# ControllerDiagrams.net
KiCad netlist of a schematic drawn in Altium Designer
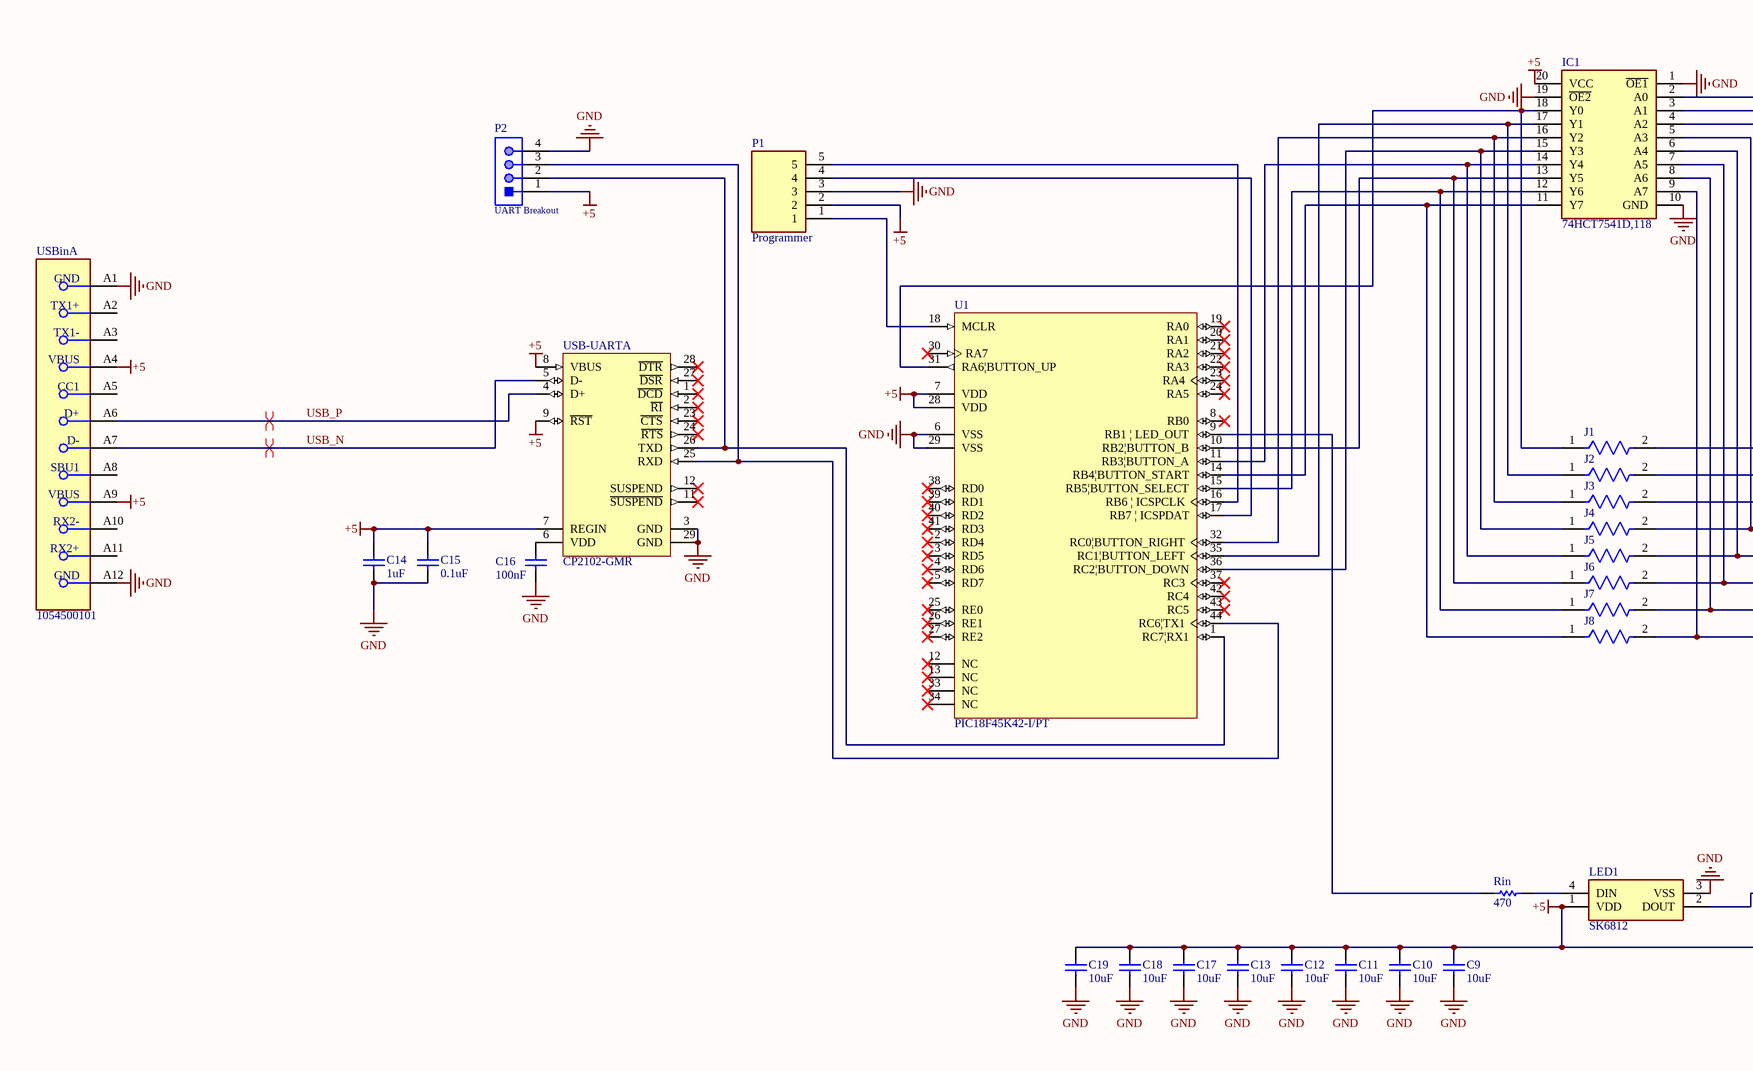
[diagram p0: ControllerDiagrams.SchDoc, left]
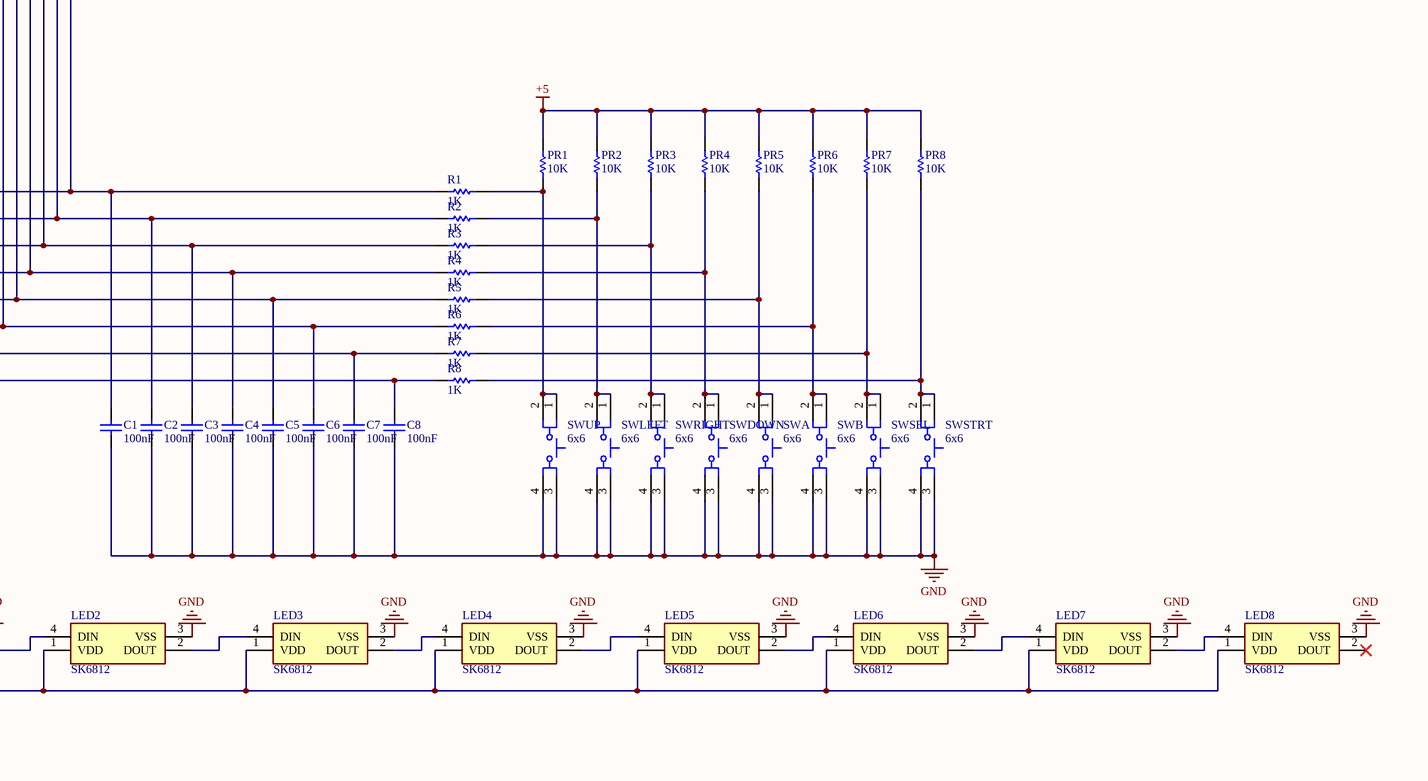
[diagram p1: ControllerDiagrams.SchDoc, right]

(export (version "E")
  (design (tool "Eeschema 10.0.6"))
  (components
    (comp (ref "C1")
      (value "100nF")
      (footprint "CAPC2013X140X50LL20T25")
      (description "Chip Capacitor, 2.2 uF, +/- 10%, 10 V, -55 to 85 degC, 0805 (2012 Metric), RoHS, Tape and Reel")
      (fields (field (name "MANUFACTURER") "AVX"))
      (libsource (lib "Altium Content Vault") (part "CAP-NP-2"))
    )
    (comp (ref "C2")
      (value "100nF")
      (footprint "CAPC2013X140X50LL20T25")
      (description "Chip Capacitor, 2.2 uF, +/- 10%, 10 V, -55 to 85 degC, 0805 (2012 Metric), RoHS, Tape and Reel")
      (fields (field (name "MANUFACTURER") "AVX"))
      (libsource (lib "Altium Content Vault") (part "CAP-NP-2"))
    )
    (comp (ref "C3")
      (value "100nF")
      (footprint "CAPC2013X140X50LL20T25")
      (description "Chip Capacitor, 2.2 uF, +/- 10%, 10 V, -55 to 85 degC, 0805 (2012 Metric), RoHS, Tape and Reel")
      (fields (field (name "MANUFACTURER") "AVX"))
      (libsource (lib "Altium Content Vault") (part "CAP-NP-2"))
    )
    (comp (ref "C4")
      (value "100nF")
      (footprint "CAPC2013X140X50LL20T25")
      (description "Chip Capacitor, 2.2 uF, +/- 10%, 10 V, -55 to 85 degC, 0805 (2012 Metric), RoHS, Tape and Reel")
      (fields (field (name "MANUFACTURER") "AVX"))
      (libsource (lib "Altium Content Vault") (part "CAP-NP-2"))
    )
    (comp (ref "C5")
      (value "100nF")
      (footprint "CAPC2013X140X50LL20T25")
      (description "Chip Capacitor, 2.2 uF, +/- 10%, 10 V, -55 to 85 degC, 0805 (2012 Metric), RoHS, Tape and Reel")
      (fields (field (name "MANUFACTURER") "AVX"))
      (libsource (lib "Altium Content Vault") (part "CAP-NP-2"))
    )
    (comp (ref "C6")
      (value "100nF")
      (footprint "CAPC2013X140X50LL20T25")
      (description "Chip Capacitor, 2.2 uF, +/- 10%, 10 V, -55 to 85 degC, 0805 (2012 Metric), RoHS, Tape and Reel")
      (fields (field (name "MANUFACTURER") "AVX"))
      (libsource (lib "Altium Content Vault") (part "CAP-NP-2"))
    )
    (comp (ref "C7")
      (value "100nF")
      (footprint "CAPC2013X140X50LL20T25")
      (description "Chip Capacitor, 2.2 uF, +/- 10%, 10 V, -55 to 85 degC, 0805 (2012 Metric), RoHS, Tape and Reel")
      (fields (field (name "MANUFACTURER") "AVX"))
      (libsource (lib "Altium Content Vault") (part "CAP-NP-2"))
    )
    (comp (ref "C8")
      (value "100nF")
      (footprint "CAPC2013X140X50LL20T25")
      (description "Chip Capacitor, 2.2 uF, +/- 10%, 10 V, -55 to 85 degC, 0805 (2012 Metric), RoHS, Tape and Reel")
      (fields (field (name "MANUFACTURER") "AVX"))
      (libsource (lib "Altium Content Vault") (part "CAP-NP-2"))
    )
    (comp (ref "C9")
      (value "10uF")
      (footprint "CAPC2013X140X50LL20T25")
      (description "Chip Capacitor, 2.2 uF, +/- 10%, 10 V, -55 to 85 degC, 0805 (2012 Metric), RoHS, Tape and Reel")
      (fields (field (name "MANUFACTURER") "AVX"))
      (libsource (lib "Altium Content Vault") (part "CAP-NP-2"))
    )
    (comp (ref "C10")
      (value "10uF")
      (footprint "CAPC2013X140X50LL20T25")
      (description "Chip Capacitor, 2.2 uF, +/- 10%, 10 V, -55 to 85 degC, 0805 (2012 Metric), RoHS, Tape and Reel")
      (fields (field (name "MANUFACTURER") "AVX"))
      (libsource (lib "Altium Content Vault") (part "CAP-NP-2"))
    )
    (comp (ref "C11")
      (value "10uF")
      (footprint "CAPC2013X140X50LL20T25")
      (description "Chip Capacitor, 2.2 uF, +/- 10%, 10 V, -55 to 85 degC, 0805 (2012 Metric), RoHS, Tape and Reel")
      (fields (field (name "MANUFACTURER") "AVX"))
      (libsource (lib "Altium Content Vault") (part "CAP-NP-2"))
    )
    (comp (ref "C12")
      (value "10uF")
      (footprint "CAPC2013X140X50LL20T25")
      (description "Chip Capacitor, 2.2 uF, +/- 10%, 10 V, -55 to 85 degC, 0805 (2012 Metric), RoHS, Tape and Reel")
      (fields (field (name "MANUFACTURER") "AVX"))
      (libsource (lib "Altium Content Vault") (part "CAP-NP-2"))
    )
    (comp (ref "C13")
      (value "10uF")
      (footprint "CAPC2013X140X50LL20T25")
      (description "Chip Capacitor, 2.2 uF, +/- 10%, 10 V, -55 to 85 degC, 0805 (2012 Metric), RoHS, Tape and Reel")
      (fields (field (name "MANUFACTURER") "AVX"))
      (libsource (lib "Altium Content Vault") (part "CAP-NP-2"))
    )
    (comp (ref "C14")
      (value "1uF")
      (footprint "CAPC2013X140X50LL20T25")
      (description "Chip Capacitor, 2.2 uF, +/- 10%, 10 V, -55 to 85 degC, 0805 (2012 Metric), RoHS, Tape and Reel")
      (fields (field (name "MANUFACTURER") "AVX"))
      (libsource (lib "Altium Content Vault") (part "CAP-NP-2"))
    )
    (comp (ref "C15")
      (value "0.1uF")
      (footprint "CAPC2013X140X50LL20T25")
      (description "Chip Capacitor, 2.2 uF, +/- 10%, 10 V, -55 to 85 degC, 0805 (2012 Metric), RoHS, Tape and Reel")
      (fields (field (name "MANUFACTURER") "AVX"))
      (libsource (lib "Altium Content Vault") (part "CAP-NP-2"))
    )
    (comp (ref "C16")
      (value "100nF")
      (footprint "CAPC2013X140X50LL20T25")
      (description "Chip Capacitor, 2.2 uF, +/- 10%, 10 V, -55 to 85 degC, 0805 (2012 Metric), RoHS, Tape and Reel")
      (fields (field (name "MANUFACTURER") "AVX"))
      (libsource (lib "Altium Content Vault") (part "CAP-NP-2"))
    )
    (comp (ref "C17")
      (value "10uF")
      (footprint "CAPC2013X140X50LL20T25")
      (description "Chip Capacitor, 2.2 uF, +/- 10%, 10 V, -55 to 85 degC, 0805 (2012 Metric), RoHS, Tape and Reel")
      (fields (field (name "MANUFACTURER") "AVX"))
      (libsource (lib "Altium Content Vault") (part "CAP-NP-2"))
    )
    (comp (ref "C18")
      (value "10uF")
      (footprint "CAPC2013X140X50LL20T25")
      (description "Chip Capacitor, 2.2 uF, +/- 10%, 10 V, -55 to 85 degC, 0805 (2012 Metric), RoHS, Tape and Reel")
      (fields (field (name "MANUFACTURER") "AVX"))
      (libsource (lib "Altium Content Vault") (part "CAP-NP-2"))
    )
    (comp (ref "C19")
      (value "10uF")
      (footprint "CAPC2013X140X50LL20T25")
      (description "Chip Capacitor, 2.2 uF, +/- 10%, 10 V, -55 to 85 degC, 0805 (2012 Metric), RoHS, Tape and Reel")
      (fields (field (name "MANUFACTURER") "AVX"))
      (libsource (lib "Altium Content Vault") (part "CAP-NP-2"))
    )
    (comp (ref "IC1")
      (value "74HCT7541D,118")
      (footprint "SamacSys:SOIC127P1032X265-20N")
      (description "Integrated Circuit")
      (fields (field (name "MOUSER PART NUMBER") "771-74HCT7541D-T"))
      (libsource (lib "*") (part "74HCT7541D,118"))
    )
    (comp (ref "J1")
      (value "~")
      (footprint "FP-ERJ-3GEY0R00V-MFG")
      (description "RES SMD 0 OHM JUMPER 1/10W 0603")
      (fields (field (name "TOLERANCE") "5%") (field (name "MANUFACTURER PART NUMBER") "ERJ-3GEY0R00V"))
      (libsource (lib "Altium Content Vault") (part "1029c3af85768c4190bb7ad29bc67b5"))
    )
    (comp (ref "J2")
      (value "~")
      (footprint "FP-ERJ-3GEY0R00V-MFG")
      (description "RES SMD 0 OHM JUMPER 1/10W 0603")
      (fields (field (name "TOLERANCE") "5%") (field (name "MANUFACTURER PART NUMBER") "ERJ-3GEY0R00V"))
      (libsource (lib "Altium Content Vault") (part "1029c3af85768c4190bb7ad29bc67b5"))
    )
    (comp (ref "J3")
      (value "~")
      (footprint "FP-ERJ-3GEY0R00V-MFG")
      (description "RES SMD 0 OHM JUMPER 1/10W 0603")
      (fields (field (name "TOLERANCE") "5%") (field (name "MANUFACTURER PART NUMBER") "ERJ-3GEY0R00V"))
      (libsource (lib "Altium Content Vault") (part "1029c3af85768c4190bb7ad29bc67b5"))
    )
    (comp (ref "J4")
      (value "~")
      (footprint "FP-ERJ-3GEY0R00V-MFG")
      (description "RES SMD 0 OHM JUMPER 1/10W 0603")
      (fields (field (name "TOLERANCE") "5%") (field (name "MANUFACTURER PART NUMBER") "ERJ-3GEY0R00V"))
      (libsource (lib "Altium Content Vault") (part "1029c3af85768c4190bb7ad29bc67b5"))
    )
    (comp (ref "J5")
      (value "~")
      (footprint "FP-ERJ-3GEY0R00V-MFG")
      (description "RES SMD 0 OHM JUMPER 1/10W 0603")
      (fields (field (name "TOLERANCE") "5%") (field (name "MANUFACTURER PART NUMBER") "ERJ-3GEY0R00V"))
      (libsource (lib "Altium Content Vault") (part "1029c3af85768c4190bb7ad29bc67b5"))
    )
    (comp (ref "J6")
      (value "~")
      (footprint "FP-ERJ-3GEY0R00V-MFG")
      (description "RES SMD 0 OHM JUMPER 1/10W 0603")
      (fields (field (name "TOLERANCE") "5%") (field (name "MANUFACTURER PART NUMBER") "ERJ-3GEY0R00V"))
      (libsource (lib "Altium Content Vault") (part "1029c3af85768c4190bb7ad29bc67b5"))
    )
    (comp (ref "J7")
      (value "~")
      (footprint "FP-ERJ-3GEY0R00V-MFG")
      (description "RES SMD 0 OHM JUMPER 1/10W 0603")
      (fields (field (name "TOLERANCE") "5%") (field (name "MANUFACTURER PART NUMBER") "ERJ-3GEY0R00V"))
      (libsource (lib "Altium Content Vault") (part "1029c3af85768c4190bb7ad29bc67b5"))
    )
    (comp (ref "J8")
      (value "~")
      (footprint "FP-ERJ-3GEY0R00V-MFG")
      (description "RES SMD 0 OHM JUMPER 1/10W 0603")
      (fields (field (name "TOLERANCE") "5%") (field (name "MANUFACTURER PART NUMBER") "ERJ-3GEY0R00V"))
      (libsource (lib "Altium Content Vault") (part "1029c3af85768c4190bb7ad29bc67b5"))
    )
    (comp (ref "LED1")
      (value "SK6812")
      (footprint "SamacSys:ILPHK501RGBWSK68120501")
      (description "LED")
      (fields (field (name "MANUFACTURER_PART_NUMBER") "ILPH-K501-RGBW-SK6812-05-01"))
      (libsource (lib "*") (part "ILPH-K501-RGBW-SK6812-05-01"))
    )
    (comp (ref "LED2")
      (value "SK6812")
      (footprint "SamacSys:ILPHK501RGBWSK68120501")
      (description "LED")
      (fields (field (name "MANUFACTURER_PART_NUMBER") "ILPH-K501-RGBW-SK6812-05-01"))
      (libsource (lib "*") (part "ILPH-K501-RGBW-SK6812-05-01"))
    )
    (comp (ref "LED3")
      (value "SK6812")
      (footprint "SamacSys:ILPHK501RGBWSK68120501")
      (description "LED")
      (fields (field (name "MANUFACTURER_PART_NUMBER") "ILPH-K501-RGBW-SK6812-05-01"))
      (libsource (lib "*") (part "ILPH-K501-RGBW-SK6812-05-01"))
    )
    (comp (ref "LED4")
      (value "SK6812")
      (footprint "SamacSys:ILPHK501RGBWSK68120501")
      (description "LED")
      (fields (field (name "MANUFACTURER_PART_NUMBER") "ILPH-K501-RGBW-SK6812-05-01"))
      (libsource (lib "*") (part "ILPH-K501-RGBW-SK6812-05-01"))
    )
    (comp (ref "LED5")
      (value "SK6812")
      (footprint "SamacSys:ILPHK501RGBWSK68120501")
      (description "LED")
      (fields (field (name "MANUFACTURER_PART_NUMBER") "ILPH-K501-RGBW-SK6812-05-01"))
      (libsource (lib "*") (part "ILPH-K501-RGBW-SK6812-05-01"))
    )
    (comp (ref "LED6")
      (value "SK6812")
      (footprint "SamacSys:ILPHK501RGBWSK68120501")
      (description "LED")
      (fields (field (name "MANUFACTURER_PART_NUMBER") "ILPH-K501-RGBW-SK6812-05-01"))
      (libsource (lib "*") (part "ILPH-K501-RGBW-SK6812-05-01"))
    )
    (comp (ref "LED7")
      (value "SK6812")
      (footprint "SamacSys:ILPHK501RGBWSK68120501")
      (description "LED")
      (fields (field (name "MANUFACTURER_PART_NUMBER") "ILPH-K501-RGBW-SK6812-05-01"))
      (libsource (lib "*") (part "ILPH-K501-RGBW-SK6812-05-01"))
    )
    (comp (ref "LED8")
      (value "SK6812")
      (footprint "SamacSys:ILPHK501RGBWSK68120501")
      (description "LED")
      (fields (field (name "MANUFACTURER_PART_NUMBER") "ILPH-K501-RGBW-SK6812-05-01"))
      (libsource (lib "*") (part "ILPH-K501-RGBW-SK6812-05-01"))
    )
    (comp (ref "P1")
      (value "Programmer")
      (footprint "SamacSys:HDRV5W64P0X254_1X5_1270X248X838P")
      (description "Connector")
      (fields
        (field (name "MANUFACTURER_PART_NUMBER") "HTSW-105-07-L-S")
        (field (name "MOUSER PART NUMBER") "200-HTSW10507LS")
      )
      (libsource (lib "*") (part "HTSW-105-07-L-S"))
    )
    (comp (ref "P2")
      (value "UART Breakout")
      (footprint "61300411121")
      (description "THT Vertical Pin Header WR-PHD, Pitch 2.54 mm, Single Row, 4 pins")
      (fields
        (field (name "MANUFACTURER") "Wurth Elektronik")
        (field (name "PART NUMBER") "61300411121")
        (field (name "PUBLISHER") "WurthElektronik")
      )
      (libsource (lib "Altium Content Vault") (part "WE-CN-1P-M-R4"))
    )
    (comp (ref "PR1")
      (value "10K")
      (footprint "RESC2013X50X30LL20T20")
      (fields (field (name "MANUFACTURER") "Vishay Dale") (field (name "PART NUMBER") "CRCW08050000Z0EA"))
      (libsource (lib "Altium Content Vault") (part "RES"))
    )
    (comp (ref "PR2")
      (value "10K")
      (footprint "RESC2013X50X30LL20T20")
      (fields (field (name "MANUFACTURER") "Vishay Dale") (field (name "PART NUMBER") "CRCW08050000Z0EA"))
      (libsource (lib "Altium Content Vault") (part "RES"))
    )
    (comp (ref "PR3")
      (value "10K")
      (footprint "RESC2013X50X30LL20T20")
      (fields (field (name "MANUFACTURER") "Vishay Dale") (field (name "PART NUMBER") "CRCW08050000Z0EA"))
      (libsource (lib "Altium Content Vault") (part "RES"))
    )
    (comp (ref "PR4")
      (value "10K")
      (footprint "RESC2013X50X30LL20T20")
      (fields (field (name "MANUFACTURER") "Vishay Dale") (field (name "PART NUMBER") "CRCW08050000Z0EA"))
      (libsource (lib "Altium Content Vault") (part "RES"))
    )
    (comp (ref "PR5")
      (value "10K")
      (footprint "RESC2013X50X30LL20T20")
      (fields (field (name "MANUFACTURER") "Vishay Dale") (field (name "PART NUMBER") "CRCW08050000Z0EA"))
      (libsource (lib "Altium Content Vault") (part "RES"))
    )
    (comp (ref "PR6")
      (value "10K")
      (footprint "RESC2013X50X30LL20T20")
      (fields (field (name "MANUFACTURER") "Vishay Dale") (field (name "PART NUMBER") "CRCW08050000Z0EA"))
      (libsource (lib "Altium Content Vault") (part "RES"))
    )
    (comp (ref "PR7")
      (value "10K")
      (footprint "RESC2013X50X30LL20T20")
      (fields (field (name "MANUFACTURER") "Vishay Dale") (field (name "PART NUMBER") "CRCW08050000Z0EA"))
      (libsource (lib "Altium Content Vault") (part "RES"))
    )
    (comp (ref "PR8")
      (value "10K")
      (footprint "RESC2013X50X30LL20T20")
      (fields (field (name "MANUFACTURER") "Vishay Dale") (field (name "PART NUMBER") "CRCW08050000Z0EA"))
      (libsource (lib "Altium Content Vault") (part "RES"))
    )
    (comp (ref "R1")
      (value "1K")
      (footprint "RESC2013X50X30LL20T20")
      (fields (field (name "MANUFACTURER") "Vishay Dale") (field (name "PART NUMBER") "CRCW08050000Z0EA"))
      (libsource (lib "Altium Content Vault") (part "RES"))
    )
    (comp (ref "R2")
      (value "1K")
      (footprint "RESC2013X50X30LL20T20")
      (fields (field (name "MANUFACTURER") "Vishay Dale") (field (name "PART NUMBER") "CRCW08050000Z0EA"))
      (libsource (lib "Altium Content Vault") (part "RES"))
    )
    (comp (ref "R3")
      (value "1K")
      (footprint "RESC2013X50X30LL20T20")
      (fields (field (name "MANUFACTURER") "Vishay Dale") (field (name "PART NUMBER") "CRCW08050000Z0EA"))
      (libsource (lib "Altium Content Vault") (part "RES"))
    )
    (comp (ref "R4")
      (value "1K")
      (footprint "RESC2013X50X30LL20T20")
      (fields (field (name "MANUFACTURER") "Vishay Dale") (field (name "PART NUMBER") "CRCW08050000Z0EA"))
      (libsource (lib "Altium Content Vault") (part "RES"))
    )
    (comp (ref "R5")
      (value "1K")
      (footprint "RESC2013X50X30LL20T20")
      (fields (field (name "MANUFACTURER") "Vishay Dale") (field (name "PART NUMBER") "CRCW08050000Z0EA"))
      (libsource (lib "Altium Content Vault") (part "RES"))
    )
    (comp (ref "R6")
      (value "1K")
      (footprint "RESC2013X50X30LL20T20")
      (fields (field (name "MANUFACTURER") "Vishay Dale") (field (name "PART NUMBER") "CRCW08050000Z0EA"))
      (libsource (lib "Altium Content Vault") (part "RES"))
    )
    (comp (ref "R7")
      (value "1K")
      (footprint "RESC2013X50X30LL20T20")
      (fields (field (name "MANUFACTURER") "Vishay Dale") (field (name "PART NUMBER") "CRCW08050000Z0EA"))
      (libsource (lib "Altium Content Vault") (part "RES"))
    )
    (comp (ref "R8")
      (value "1K")
      (footprint "RESC2013X50X30LL20T20")
      (fields (field (name "MANUFACTURER") "Vishay Dale") (field (name "PART NUMBER") "CRCW08050000Z0EA"))
      (libsource (lib "Altium Content Vault") (part "RES"))
    )
    (comp (ref "Rin")
      (value "470")
      (footprint "RESC2013X50X30LL20T20")
      (fields (field (name "MANUFACTURER") "Vishay Dale") (field (name "PART NUMBER") "CRCW08050000Z0EA"))
      (libsource (lib "Altium Content Vault") (part "RES"))
    )
    (comp (ref "SWA")
      (value "6x6")
      (footprint "ESWI-TL1105SPF_V")
      (description "Tact Switch, SPST-NO, 50 mA, 12 VDC, -20 to 70 degC, 4-Pin THD, RoHS, Bulk")
      (fields (field (name "MANUFACTURER") "E-Switch"))
      (libsource (lib "Altium Content Vault") (part "SW-SPST-NO-4"))
    )
    (comp (ref "SWB")
      (value "6x6")
      (footprint "ESWI-TL1105SPF_V")
      (description "Tact Switch, SPST-NO, 50 mA, 12 VDC, -20 to 70 degC, 4-Pin THD, RoHS, Bulk")
      (fields (field (name "MANUFACTURER") "E-Switch"))
      (libsource (lib "Altium Content Vault") (part "SW-SPST-NO-4"))
    )
    (comp (ref "SWDOWN")
      (value "6x6")
      (footprint "ESWI-TL1105SPF_V")
      (description "Tact Switch, SPST-NO, 50 mA, 12 VDC, -20 to 70 degC, 4-Pin THD, RoHS, Bulk")
      (fields (field (name "MANUFACTURER") "E-Switch"))
      (libsource (lib "Altium Content Vault") (part "SW-SPST-NO-4"))
    )
    (comp (ref "SWLEFT")
      (value "6x6")
      (footprint "ESWI-TL1105SPF_V")
      (description "Tact Switch, SPST-NO, 50 mA, 12 VDC, -20 to 70 degC, 4-Pin THD, RoHS, Bulk")
      (fields (field (name "MANUFACTURER") "E-Switch"))
      (libsource (lib "Altium Content Vault") (part "SW-SPST-NO-4"))
    )
    (comp (ref "SWRIGHT")
      (value "6x6")
      (footprint "ESWI-TL1105SPF_V")
      (description "Tact Switch, SPST-NO, 50 mA, 12 VDC, -20 to 70 degC, 4-Pin THD, RoHS, Bulk")
      (fields (field (name "MANUFACTURER") "E-Switch"))
      (libsource (lib "Altium Content Vault") (part "SW-SPST-NO-4"))
    )
    (comp (ref "SWSEL")
      (value "6x6")
      (footprint "ESWI-TL1105SPF_V")
      (description "Tact Switch, SPST-NO, 50 mA, 12 VDC, -20 to 70 degC, 4-Pin THD, RoHS, Bulk")
      (fields (field (name "MANUFACTURER") "E-Switch"))
      (libsource (lib "Altium Content Vault") (part "SW-SPST-NO-4"))
    )
    (comp (ref "SWSTRT")
      (value "6x6")
      (footprint "ESWI-TL1105SPF_V")
      (description "Tact Switch, SPST-NO, 50 mA, 12 VDC, -20 to 70 degC, 4-Pin THD, RoHS, Bulk")
      (fields (field (name "MANUFACTURER") "E-Switch"))
      (libsource (lib "Altium Content Vault") (part "SW-SPST-NO-4"))
    )
    (comp (ref "SWUP")
      (value "6x6")
      (footprint "ESWI-TL1105SPF_V")
      (description "Tact Switch, SPST-NO, 50 mA, 12 VDC, -20 to 70 degC, 4-Pin THD, RoHS, Bulk")
      (fields (field (name "MANUFACTURER") "E-Switch"))
      (libsource (lib "Altium Content Vault") (part "SW-SPST-NO-4"))
    )
    (comp (ref "U1")
      (value "PIC18F45K42-I/PT")
      (footprint "TQFP-PT44_M")
      (libsource (lib "Altium Content Vault") (part "MC-8B-16F874A-SQ44B"))
    )
    (comp (ref "USB-UART")
      (value "CP2102-GMR")
      (footprint "SLAB-QFN-28-3125x3125TP_M")
      (description "Single-Chip USB to URAT Bridge, 3.3 V, -40 to 85 degC, 28-Pin QFN, RoHS, Tape and Reel")
      (fields (field (name "MANUFACTURER") "Silicon Labs"))
      (libsource (lib "Altium Content Vault") (part "SLAB-CP210X-QFN-28-29"))
    )
    (comp (ref "USBin")
      (value "1054500101")
      (footprint "FP-1054500101-MFG")
      (description "CONN RCP USB3.1 TYPEC 24P SMD RA")
      (fields
        (field (name "MANUFACTURER") "Molex")
        (field (name "OCTOPART") "https://octopart.com/105450-0101-molex-68082325")
      )
      (libsource (lib "Altium Content Vault") (part "9808b19ecaf079fb99eed69f0495cd0"))
    )
  )
  (nets
    (net (code "1") (name "+5") (class "Default")
      (node (ref "C10") (pin "2") (pinfunction "2_2") (pintype "passive"))
      (node (ref "C11") (pin "2") (pinfunction "2_2") (pintype "passive"))
      (node (ref "C12") (pin "2") (pinfunction "2_2") (pintype "passive"))
      (node (ref "C13") (pin "2") (pinfunction "2_2") (pintype "passive"))
      (node (ref "C14") (pin "2") (pinfunction "2_2") (pintype "passive"))
      (node (ref "C15") (pin "2") (pinfunction "2_2") (pintype "passive"))
      (node (ref "C17") (pin "2") (pinfunction "2_2") (pintype "passive"))
      (node (ref "C18") (pin "2") (pinfunction "2_2") (pintype "passive"))
      (node (ref "C19") (pin "2") (pinfunction "2_2") (pintype "passive"))
      (node (ref "C9") (pin "2") (pinfunction "2_2") (pintype "passive"))
      (node (ref "IC1") (pin "20") (pinfunction "VCC_20") (pintype "passive"))
      (node (ref "LED1") (pin "1") (pinfunction "VDD_1") (pintype "passive"))
      (node (ref "LED2") (pin "1") (pinfunction "VDD_1") (pintype "passive"))
      (node (ref "LED3") (pin "1") (pinfunction "VDD_1") (pintype "passive"))
      (node (ref "LED4") (pin "1") (pinfunction "VDD_1") (pintype "passive"))
      (node (ref "LED5") (pin "1") (pinfunction "VDD_1") (pintype "passive"))
      (node (ref "LED6") (pin "1") (pinfunction "VDD_1") (pintype "passive"))
      (node (ref "LED7") (pin "1") (pinfunction "VDD_1") (pintype "passive"))
      (node (ref "LED8") (pin "1") (pinfunction "VDD_1") (pintype "passive"))
      (node (ref "P1") (pin "2") (pinfunction "2_2") (pintype "passive"))
      (node (ref "P2") (pin "1") (pinfunction "1_1") (pintype "passive"))
      (node (ref "PR1") (pin "2") (pinfunction "2_2") (pintype "passive"))
      (node (ref "PR2") (pin "2") (pinfunction "2_2") (pintype "passive"))
      (node (ref "PR3") (pin "2") (pinfunction "2_2") (pintype "passive"))
      (node (ref "PR4") (pin "2") (pinfunction "2_2") (pintype "passive"))
      (node (ref "PR5") (pin "2") (pinfunction "2_2") (pintype "passive"))
      (node (ref "PR6") (pin "2") (pinfunction "2_2") (pintype "passive"))
      (node (ref "PR7") (pin "2") (pinfunction "2_2") (pintype "passive"))
      (node (ref "PR8") (pin "2") (pinfunction "2_2") (pintype "passive"))
      (node (ref "U1") (pin "28") (pinfunction "VDD_28") (pintype "power_in"))
      (node (ref "U1") (pin "7") (pinfunction "VDD_7") (pintype "power_in"))
      (node (ref "USB-UART") (pin "7") (pinfunction "REGIN_7") (pintype "power_in"))
      (node (ref "USB-UART") (pin "8") (pinfunction "VBUS_8") (pintype "input"))
      (node (ref "USB-UART") (pin "9") (pinfunction "~{RST}_9") (pintype "bidirectional"))
      (node (ref "USBin") (pin "A4") (pinfunction "VBUS_A4") (pintype "passive"))
      (node (ref "USBin") (pin "A9") (pinfunction "VBUS_A9") (pintype "passive"))
    )
    (net (code "2") (name "/USB_N") (class "Default")
      (node (ref "USB-UART") (pin "5") (pinfunction "D-_5") (pintype "bidirectional"))
      (node (ref "USBin") (pin "A7") (pinfunction "D-_A7") (pintype "passive"))
    )
    (net (code "3") (name "/USB_P") (class "Default")
      (node (ref "USB-UART") (pin "4") (pinfunction "D+_4") (pintype "bidirectional"))
      (node (ref "USBin") (pin "A6") (pinfunction "D+_A6") (pintype "passive"))
    )
    (net (code "4") (name "GND") (class "Default")
      (node (ref "C1") (pin "1") (pinfunction "1_1") (pintype "passive"))
      (node (ref "C10") (pin "1") (pinfunction "1_1") (pintype "passive"))
      (node (ref "C11") (pin "1") (pinfunction "1_1") (pintype "passive"))
      (node (ref "C12") (pin "1") (pinfunction "1_1") (pintype "passive"))
      (node (ref "C13") (pin "1") (pinfunction "1_1") (pintype "passive"))
      (node (ref "C14") (pin "1") (pinfunction "1_1") (pintype "passive"))
      (node (ref "C15") (pin "1") (pinfunction "1_1") (pintype "passive"))
      (node (ref "C16") (pin "2") (pinfunction "2_2") (pintype "passive"))
      (node (ref "C17") (pin "1") (pinfunction "1_1") (pintype "passive"))
      (node (ref "C18") (pin "1") (pinfunction "1_1") (pintype "passive"))
      (node (ref "C19") (pin "1") (pinfunction "1_1") (pintype "passive"))
      (node (ref "C2") (pin "1") (pinfunction "1_1") (pintype "passive"))
      (node (ref "C3") (pin "1") (pinfunction "1_1") (pintype "passive"))
      (node (ref "C4") (pin "1") (pinfunction "1_1") (pintype "passive"))
      (node (ref "C5") (pin "1") (pinfunction "1_1") (pintype "passive"))
      (node (ref "C6") (pin "1") (pinfunction "1_1") (pintype "passive"))
      (node (ref "C7") (pin "1") (pinfunction "1_1") (pintype "passive"))
      (node (ref "C8") (pin "1") (pinfunction "1_1") (pintype "passive"))
      (node (ref "C9") (pin "1") (pinfunction "1_1") (pintype "passive"))
      (node (ref "IC1") (pin "1") (pinfunction "~{OE1}_1") (pintype "passive"))
      (node (ref "IC1") (pin "10") (pinfunction "GND_10") (pintype "passive"))
      (node (ref "IC1") (pin "19") (pinfunction "~{OE2}_19") (pintype "passive"))
      (node (ref "LED1") (pin "3") (pinfunction "VSS_3") (pintype "passive"))
      (node (ref "LED2") (pin "3") (pinfunction "VSS_3") (pintype "passive"))
      (node (ref "LED3") (pin "3") (pinfunction "VSS_3") (pintype "passive"))
      (node (ref "LED4") (pin "3") (pinfunction "VSS_3") (pintype "passive"))
      (node (ref "LED5") (pin "3") (pinfunction "VSS_3") (pintype "passive"))
      (node (ref "LED6") (pin "3") (pinfunction "VSS_3") (pintype "passive"))
      (node (ref "LED7") (pin "3") (pinfunction "VSS_3") (pintype "passive"))
      (node (ref "LED8") (pin "3") (pinfunction "VSS_3") (pintype "passive"))
      (node (ref "P1") (pin "3") (pinfunction "3_3") (pintype "passive"))
      (node (ref "P2") (pin "4") (pinfunction "4_4") (pintype "passive"))
      (node (ref "SWA") (pin "3") (pinfunction "3_3") (pintype "passive"))
      (node (ref "SWA") (pin "4") (pinfunction "4_4") (pintype "passive"))
      (node (ref "SWB") (pin "3") (pinfunction "3_3") (pintype "passive"))
      (node (ref "SWB") (pin "4") (pinfunction "4_4") (pintype "passive"))
      (node (ref "SWDOWN") (pin "3") (pinfunction "3_3") (pintype "passive"))
      (node (ref "SWDOWN") (pin "4") (pinfunction "4_4") (pintype "passive"))
      (node (ref "SWLEFT") (pin "3") (pinfunction "3_3") (pintype "passive"))
      (node (ref "SWLEFT") (pin "4") (pinfunction "4_4") (pintype "passive"))
      (node (ref "SWRIGHT") (pin "3") (pinfunction "3_3") (pintype "passive"))
      (node (ref "SWRIGHT") (pin "4") (pinfunction "4_4") (pintype "passive"))
      (node (ref "SWSEL") (pin "3") (pinfunction "3_3") (pintype "passive"))
      (node (ref "SWSEL") (pin "4") (pinfunction "4_4") (pintype "passive"))
      (node (ref "SWSTRT") (pin "3") (pinfunction "3_3") (pintype "passive"))
      (node (ref "SWSTRT") (pin "4") (pinfunction "4_4") (pintype "passive"))
      (node (ref "SWUP") (pin "3") (pinfunction "3_3") (pintype "passive"))
      (node (ref "SWUP") (pin "4") (pinfunction "4_4") (pintype "passive"))
      (node (ref "U1") (pin "29") (pinfunction "VSS_29") (pintype "power_in"))
      (node (ref "U1") (pin "6") (pinfunction "VSS_6") (pintype "power_in"))
      (node (ref "USB-UART") (pin "29") (pinfunction "GND_29") (pintype "power_in"))
      (node (ref "USB-UART") (pin "3") (pinfunction "GND_3") (pintype "power_in"))
      (node (ref "USBin") (pin "A1") (pinfunction "GND_A1") (pintype "passive"))
      (node (ref "USBin") (pin "A12") (pinfunction "GND_A12") (pintype "passive"))
    )
    (net (code "5") (name "Net-(IC1-A0)") (class "Default")
      (node (ref "C1") (pin "2") (pinfunction "2_2") (pintype "passive"))
      (node (ref "IC1") (pin "2") (pinfunction "A0_2") (pintype "passive"))
      (node (ref "J1") (pin "2") (pinfunction "2_2") (pintype "passive"))
      (node (ref "R1") (pin "2") (pinfunction "2_2") (pintype "passive"))
    )
    (net (code "6") (name "Net-(IC1-A1)") (class "Default")
      (node (ref "C2") (pin "2") (pinfunction "2_2") (pintype "passive"))
      (node (ref "IC1") (pin "3") (pinfunction "A1_3") (pintype "passive"))
      (node (ref "J2") (pin "2") (pinfunction "2_2") (pintype "passive"))
      (node (ref "R2") (pin "2") (pinfunction "2_2") (pintype "passive"))
    )
    (net (code "7") (name "Net-(IC1-A2)") (class "Default")
      (node (ref "C3") (pin "2") (pinfunction "2_2") (pintype "passive"))
      (node (ref "IC1") (pin "4") (pinfunction "A2_4") (pintype "passive"))
      (node (ref "J3") (pin "2") (pinfunction "2_2") (pintype "passive"))
      (node (ref "R3") (pin "2") (pinfunction "2_2") (pintype "passive"))
    )
    (net (code "8") (name "Net-(IC1-A3)") (class "Default")
      (node (ref "C4") (pin "2") (pinfunction "2_2") (pintype "passive"))
      (node (ref "IC1") (pin "5") (pinfunction "A3_5") (pintype "passive"))
      (node (ref "J4") (pin "2") (pinfunction "2_2") (pintype "passive"))
      (node (ref "R4") (pin "2") (pinfunction "2_2") (pintype "passive"))
    )
    (net (code "9") (name "Net-(IC1-A4)") (class "Default")
      (node (ref "C5") (pin "2") (pinfunction "2_2") (pintype "passive"))
      (node (ref "IC1") (pin "6") (pinfunction "A4_6") (pintype "passive"))
      (node (ref "J5") (pin "2") (pinfunction "2_2") (pintype "passive"))
      (node (ref "R5") (pin "2") (pinfunction "2_2") (pintype "passive"))
    )
    (net (code "10") (name "Net-(IC1-A5)") (class "Default")
      (node (ref "C6") (pin "2") (pinfunction "2_2") (pintype "passive"))
      (node (ref "IC1") (pin "7") (pinfunction "A5_7") (pintype "passive"))
      (node (ref "J6") (pin "2") (pinfunction "2_2") (pintype "passive"))
      (node (ref "R6") (pin "2") (pinfunction "2_2") (pintype "passive"))
    )
    (net (code "11") (name "Net-(IC1-A6)") (class "Default")
      (node (ref "C7") (pin "2") (pinfunction "2_2") (pintype "passive"))
      (node (ref "IC1") (pin "8") (pinfunction "A6_8") (pintype "passive"))
      (node (ref "J7") (pin "2") (pinfunction "2_2") (pintype "passive"))
      (node (ref "R7") (pin "2") (pinfunction "2_2") (pintype "passive"))
    )
    (net (code "12") (name "Net-(IC1-A7)") (class "Default")
      (node (ref "C8") (pin "2") (pinfunction "2_2") (pintype "passive"))
      (node (ref "IC1") (pin "9") (pinfunction "A7_9") (pintype "passive"))
      (node (ref "J8") (pin "2") (pinfunction "2_2") (pintype "passive"))
      (node (ref "R8") (pin "2") (pinfunction "2_2") (pintype "passive"))
    )
    (net (code "13") (name "Net-(IC1-Y0)") (class "Default")
      (node (ref "IC1") (pin "18") (pinfunction "Y0_18") (pintype "passive"))
      (node (ref "J1") (pin "1") (pinfunction "1_1") (pintype "passive"))
      (node (ref "U1") (pin "31") (pinfunction "RA6¦BUTTON_UP_31") (pintype "output"))
    )
    (net (code "14") (name "Net-(IC1-Y1)") (class "Default")
      (node (ref "IC1") (pin "17") (pinfunction "Y1_17") (pintype "passive"))
      (node (ref "J2") (pin "1") (pinfunction "1_1") (pintype "passive"))
      (node (ref "U1") (pin "35") (pinfunction "RC1¦BUTTON_LEFT_35") (pintype "bidirectional"))
    )
    (net (code "15") (name "Net-(IC1-Y2)") (class "Default")
      (node (ref "IC1") (pin "16") (pinfunction "Y2_16") (pintype "passive"))
      (node (ref "J3") (pin "1") (pinfunction "1_1") (pintype "passive"))
      (node (ref "U1") (pin "32") (pinfunction "RC0¦BUTTON_RIGHT_32") (pintype "bidirectional"))
    )
    (net (code "16") (name "Net-(IC1-Y3)") (class "Default")
      (node (ref "IC1") (pin "15") (pinfunction "Y3_15") (pintype "passive"))
      (node (ref "J4") (pin "1") (pinfunction "1_1") (pintype "passive"))
      (node (ref "U1") (pin "36") (pinfunction "RC2¦BUTTON_DOWN_36") (pintype "bidirectional"))
    )
    (net (code "17") (name "Net-(IC1-Y4)") (class "Default")
      (node (ref "IC1") (pin "14") (pinfunction "Y4_14") (pintype "passive"))
      (node (ref "J5") (pin "1") (pinfunction "1_1") (pintype "passive"))
      (node (ref "U1") (pin "11") (pinfunction "RB3¦BUTTON_A_11") (pintype "bidirectional"))
    )
    (net (code "18") (name "Net-(IC1-Y5)") (class "Default")
      (node (ref "IC1") (pin "13") (pinfunction "Y5_13") (pintype "passive"))
      (node (ref "J6") (pin "1") (pinfunction "1_1") (pintype "passive"))
      (node (ref "U1") (pin "10") (pinfunction "RB2¦BUTTON_B_10") (pintype "bidirectional"))
    )
    (net (code "19") (name "Net-(IC1-Y6)") (class "Default")
      (node (ref "IC1") (pin "12") (pinfunction "Y6_12") (pintype "passive"))
      (node (ref "J7") (pin "1") (pinfunction "1_1") (pintype "passive"))
      (node (ref "U1") (pin "15") (pinfunction "RB5¦BUTTON_SELECT_15") (pintype "bidirectional"))
    )
    (net (code "20") (name "Net-(IC1-Y7)") (class "Default")
      (node (ref "IC1") (pin "11") (pinfunction "Y7_11") (pintype "passive"))
      (node (ref "J8") (pin "1") (pinfunction "1_1") (pintype "passive"))
      (node (ref "U1") (pin "14") (pinfunction "RB4¦BUTTON_START_14") (pintype "bidirectional"))
    )
    (net (code "21") (name "Net-(LED1-DIN)") (class "Default")
      (node (ref "LED1") (pin "4") (pinfunction "DIN_4") (pintype "passive"))
      (node (ref "Rin") (pin "2") (pinfunction "2_2") (pintype "passive"))
    )
    (net (code "22") (name "Net-(LED1-DOUT)") (class "Default")
      (node (ref "LED1") (pin "2") (pinfunction "DOUT_2") (pintype "passive"))
      (node (ref "LED2") (pin "4") (pinfunction "DIN_4") (pintype "passive"))
    )
    (net (code "23") (name "Net-(LED2-DOUT)") (class "Default")
      (node (ref "LED2") (pin "2") (pinfunction "DOUT_2") (pintype "passive"))
      (node (ref "LED3") (pin "4") (pinfunction "DIN_4") (pintype "passive"))
    )
    (net (code "24") (name "Net-(LED3-DOUT)") (class "Default")
      (node (ref "LED3") (pin "2") (pinfunction "DOUT_2") (pintype "passive"))
      (node (ref "LED4") (pin "4") (pinfunction "DIN_4") (pintype "passive"))
    )
    (net (code "25") (name "Net-(LED4-DOUT)") (class "Default")
      (node (ref "LED4") (pin "2") (pinfunction "DOUT_2") (pintype "passive"))
      (node (ref "LED5") (pin "4") (pinfunction "DIN_4") (pintype "passive"))
    )
    (net (code "26") (name "Net-(LED5-DOUT)") (class "Default")
      (node (ref "LED5") (pin "2") (pinfunction "DOUT_2") (pintype "passive"))
      (node (ref "LED6") (pin "4") (pinfunction "DIN_4") (pintype "passive"))
    )
    (net (code "27") (name "Net-(LED6-DOUT)") (class "Default")
      (node (ref "LED6") (pin "2") (pinfunction "DOUT_2") (pintype "passive"))
      (node (ref "LED7") (pin "4") (pinfunction "DIN_4") (pintype "passive"))
    )
    (net (code "28") (name "Net-(LED7-DOUT)") (class "Default")
      (node (ref "LED7") (pin "2") (pinfunction "DOUT_2") (pintype "passive"))
      (node (ref "LED8") (pin "4") (pinfunction "DIN_4") (pintype "passive"))
    )
    (net (code "29") (name "Net-(PR1-Pad1)") (class "Default")
      (node (ref "PR1") (pin "1") (pinfunction "1_1") (pintype "passive"))
      (node (ref "R1") (pin "1") (pinfunction "1_1") (pintype "passive"))
      (node (ref "SWUP") (pin "1") (pinfunction "1_1") (pintype "passive"))
      (node (ref "SWUP") (pin "2") (pinfunction "2_2") (pintype "passive"))
    )
    (net (code "30") (name "Net-(PR2-Pad1)") (class "Default")
      (node (ref "PR2") (pin "1") (pinfunction "1_1") (pintype "passive"))
      (node (ref "R2") (pin "1") (pinfunction "1_1") (pintype "passive"))
      (node (ref "SWLEFT") (pin "1") (pinfunction "1_1") (pintype "passive"))
      (node (ref "SWLEFT") (pin "2") (pinfunction "2_2") (pintype "passive"))
    )
    (net (code "31") (name "Net-(PR3-Pad1)") (class "Default")
      (node (ref "PR3") (pin "1") (pinfunction "1_1") (pintype "passive"))
      (node (ref "R3") (pin "1") (pinfunction "1_1") (pintype "passive"))
      (node (ref "SWRIGHT") (pin "1") (pinfunction "1_1") (pintype "passive"))
      (node (ref "SWRIGHT") (pin "2") (pinfunction "2_2") (pintype "passive"))
    )
    (net (code "32") (name "Net-(PR4-Pad1)") (class "Default")
      (node (ref "PR4") (pin "1") (pinfunction "1_1") (pintype "passive"))
      (node (ref "R4") (pin "1") (pinfunction "1_1") (pintype "passive"))
      (node (ref "SWDOWN") (pin "1") (pinfunction "1_1") (pintype "passive"))
      (node (ref "SWDOWN") (pin "2") (pinfunction "2_2") (pintype "passive"))
    )
    (net (code "33") (name "Net-(PR5-Pad1)") (class "Default")
      (node (ref "PR5") (pin "1") (pinfunction "1_1") (pintype "passive"))
      (node (ref "R5") (pin "1") (pinfunction "1_1") (pintype "passive"))
      (node (ref "SWA") (pin "1") (pinfunction "1_1") (pintype "passive"))
      (node (ref "SWA") (pin "2") (pinfunction "2_2") (pintype "passive"))
    )
    (net (code "34") (name "Net-(PR6-Pad1)") (class "Default")
      (node (ref "PR6") (pin "1") (pinfunction "1_1") (pintype "passive"))
      (node (ref "R6") (pin "1") (pinfunction "1_1") (pintype "passive"))
      (node (ref "SWB") (pin "1") (pinfunction "1_1") (pintype "passive"))
      (node (ref "SWB") (pin "2") (pinfunction "2_2") (pintype "passive"))
    )
    (net (code "35") (name "Net-(PR7-Pad1)") (class "Default")
      (node (ref "PR7") (pin "1") (pinfunction "1_1") (pintype "passive"))
      (node (ref "R7") (pin "1") (pinfunction "1_1") (pintype "passive"))
      (node (ref "SWSEL") (pin "1") (pinfunction "1_1") (pintype "passive"))
      (node (ref "SWSEL") (pin "2") (pinfunction "2_2") (pintype "passive"))
    )
    (net (code "36") (name "Net-(PR8-Pad1)") (class "Default")
      (node (ref "PR8") (pin "1") (pinfunction "1_1") (pintype "passive"))
      (node (ref "R8") (pin "1") (pinfunction "1_1") (pintype "passive"))
      (node (ref "SWSTRT") (pin "1") (pinfunction "1_1") (pintype "passive"))
      (node (ref "SWSTRT") (pin "2") (pinfunction "2_2") (pintype "passive"))
    )
    (net (code "37") (name "Net-(U1-MCLR)") (class "Default")
      (node (ref "P1") (pin "1") (pinfunction "1_1") (pintype "passive"))
      (node (ref "U1") (pin "18") (pinfunction "MCLR_18") (pintype "input"))
    )
    (net (code "38") (name "Net-(U1-RB1_¦_LED_OUT)") (class "Default")
      (node (ref "Rin") (pin "1") (pinfunction "1_1") (pintype "passive"))
      (node (ref "U1") (pin "9") (pinfunction "RB1_¦_LED_OUT_9") (pintype "bidirectional"))
    )
    (net (code "39") (name "Net-(U1-RB6_¦_ICSPCLK)") (class "Default")
      (node (ref "P1") (pin "5") (pinfunction "5_5") (pintype "passive"))
      (node (ref "U1") (pin "16") (pinfunction "RB6_¦_ICSPCLK_16") (pintype "bidirectional"))
    )
    (net (code "40") (name "Net-(U1-RB7_¦_ICSPDAT)") (class "Default")
      (node (ref "P1") (pin "4") (pinfunction "4_4") (pintype "passive"))
      (node (ref "U1") (pin "17") (pinfunction "RB7_¦_ICSPDAT_17") (pintype "bidirectional"))
    )
    (net (code "41") (name "Net-(U1-RC6¦TX1)") (class "Default")
      (node (ref "P2") (pin "3") (pinfunction "3_3") (pintype "passive"))
      (node (ref "U1") (pin "44") (pinfunction "RC6¦TX1_44") (pintype "bidirectional"))
      (node (ref "USB-UART") (pin "25") (pinfunction "RXD_25") (pintype "input"))
    )
    (net (code "42") (name "Net-(U1-RC7¦RX1)") (class "Default")
      (node (ref "P2") (pin "2") (pinfunction "2_2") (pintype "passive"))
      (node (ref "U1") (pin "1") (pinfunction "RC7¦RX1_1") (pintype "bidirectional"))
      (node (ref "USB-UART") (pin "26") (pinfunction "TXD_26") (pintype "output"))
    )
    (net (code "43") (name "Net-(USB-UARTA-VDD)") (class "Default")
      (node (ref "C16") (pin "1") (pinfunction "1_1") (pintype "passive"))
      (node (ref "USB-UART") (pin "6") (pinfunction "VDD_6") (pintype "power_in"))
    )
    (net (code "44") (name "unconnected-(LED8-DOUT-Pad2)") (class "Default")
      (node (ref "LED8") (pin "2") (pinfunction "DOUT_2") (pintype "passive+no_connect"))
    )
    (net (code "45") (name "unconnected-(U1-NC-Pad12)") (class "Default")
      (node (ref "U1") (pin "12") (pinfunction "NC_12") (pintype "passive+no_connect"))
    )
    (net (code "46") (name "unconnected-(U1-NC-Pad13)") (class "Default")
      (node (ref "U1") (pin "13") (pinfunction "NC_13") (pintype "passive+no_connect"))
    )
    (net (code "47") (name "unconnected-(U1-NC-Pad33)") (class "Default")
      (node (ref "U1") (pin "33") (pinfunction "NC_33") (pintype "passive+no_connect"))
    )
    (net (code "48") (name "unconnected-(U1-NC-Pad34)") (class "Default")
      (node (ref "U1") (pin "34") (pinfunction "NC_34") (pintype "passive+no_connect"))
    )
    (net (code "49") (name "unconnected-(U1-RA0-Pad19)") (class "Default")
      (node (ref "U1") (pin "19") (pinfunction "RA0_19") (pintype "bidirectional+no_connect"))
    )
    (net (code "50") (name "unconnected-(U1-RA1-Pad20)") (class "Default")
      (node (ref "U1") (pin "20") (pinfunction "RA1_20") (pintype "bidirectional+no_connect"))
    )
    (net (code "51") (name "unconnected-(U1-RA2-Pad21)") (class "Default")
      (node (ref "U1") (pin "21") (pinfunction "RA2_21") (pintype "bidirectional+no_connect"))
    )
    (net (code "52") (name "unconnected-(U1-RA3-Pad22)") (class "Default")
      (node (ref "U1") (pin "22") (pinfunction "RA3_22") (pintype "bidirectional+no_connect"))
    )
    (net (code "53") (name "unconnected-(U1-RA4-Pad23)") (class "Default")
      (node (ref "U1") (pin "23") (pinfunction "RA4_23") (pintype "bidirectional+no_connect"))
    )
    (net (code "54") (name "unconnected-(U1-RA5-Pad24)") (class "Default")
      (node (ref "U1") (pin "24") (pinfunction "RA5_24") (pintype "bidirectional+no_connect"))
    )
    (net (code "55") (name "unconnected-(U1-RA7-Pad30)") (class "Default")
      (node (ref "U1") (pin "30") (pinfunction "RA7_30") (pintype "input+no_connect"))
    )
    (net (code "56") (name "unconnected-(U1-RB0-Pad8)") (class "Default")
      (node (ref "U1") (pin "8") (pinfunction "RB0_8") (pintype "bidirectional+no_connect"))
    )
    (net (code "57") (name "unconnected-(U1-RC3-Pad37)") (class "Default")
      (node (ref "U1") (pin "37") (pinfunction "RC3_37") (pintype "bidirectional+no_connect"))
    )
    (net (code "58") (name "unconnected-(U1-RC4-Pad42)") (class "Default")
      (node (ref "U1") (pin "42") (pinfunction "RC4_42") (pintype "bidirectional+no_connect"))
    )
    (net (code "59") (name "unconnected-(U1-RC5-Pad43)") (class "Default")
      (node (ref "U1") (pin "43") (pinfunction "RC5_43") (pintype "bidirectional+no_connect"))
    )
    (net (code "60") (name "unconnected-(U1-RD0-Pad38)") (class "Default")
      (node (ref "U1") (pin "38") (pinfunction "RD0_38") (pintype "bidirectional+no_connect"))
    )
    (net (code "61") (name "unconnected-(U1-RD1-Pad39)") (class "Default")
      (node (ref "U1") (pin "39") (pinfunction "RD1_39") (pintype "bidirectional+no_connect"))
    )
    (net (code "62") (name "unconnected-(U1-RD2-Pad40)") (class "Default")
      (node (ref "U1") (pin "40") (pinfunction "RD2_40") (pintype "bidirectional+no_connect"))
    )
    (net (code "63") (name "unconnected-(U1-RD3-Pad41)") (class "Default")
      (node (ref "U1") (pin "41") (pinfunction "RD3_41") (pintype "bidirectional+no_connect"))
    )
    (net (code "64") (name "unconnected-(U1-RD4-Pad2)") (class "Default")
      (node (ref "U1") (pin "2") (pinfunction "RD4_2") (pintype "bidirectional+no_connect"))
    )
    (net (code "65") (name "unconnected-(U1-RD5-Pad3)") (class "Default")
      (node (ref "U1") (pin "3") (pinfunction "RD5_3") (pintype "bidirectional+no_connect"))
    )
    (net (code "66") (name "unconnected-(U1-RD6-Pad4)") (class "Default")
      (node (ref "U1") (pin "4") (pinfunction "RD6_4") (pintype "bidirectional+no_connect"))
    )
    (net (code "67") (name "unconnected-(U1-RD7-Pad5)") (class "Default")
      (node (ref "U1") (pin "5") (pinfunction "RD7_5") (pintype "bidirectional+no_connect"))
    )
    (net (code "68") (name "unconnected-(U1-RE0-Pad25)") (class "Default")
      (node (ref "U1") (pin "25") (pinfunction "RE0_25") (pintype "bidirectional+no_connect"))
    )
    (net (code "69") (name "unconnected-(U1-RE1-Pad26)") (class "Default")
      (node (ref "U1") (pin "26") (pinfunction "RE1_26") (pintype "bidirectional+no_connect"))
    )
    (net (code "70") (name "unconnected-(U1-RE2-Pad27)") (class "Default")
      (node (ref "U1") (pin "27") (pinfunction "RE2_27") (pintype "bidirectional+no_connect"))
    )
    (net (code "71") (name "unconnected-(USB-UARTA-SUSPEND-Pad12)") (class "Default")
      (node (ref "USB-UART") (pin "12") (pinfunction "SUSPEND_12") (pintype "output+no_connect"))
    )
    (net (code "72") (name "unconnected-(USB-UARTA-~{CTS}-Pad23)") (class "Default")
      (node (ref "USB-UART") (pin "23") (pinfunction "~{CTS}_23") (pintype "input+no_connect"))
    )
    (net (code "73") (name "unconnected-(USB-UARTA-~{DCD}-Pad1)") (class "Default")
      (node (ref "USB-UART") (pin "1") (pinfunction "~{DCD}_1") (pintype "input+no_connect"))
    )
    (net (code "74") (name "unconnected-(USB-UARTA-~{DSR}-Pad27)") (class "Default")
      (node (ref "USB-UART") (pin "27") (pinfunction "~{DSR}_27") (pintype "input+no_connect"))
    )
    (net (code "75") (name "unconnected-(USB-UARTA-~{DTR}-Pad28)") (class "Default")
      (node (ref "USB-UART") (pin "28") (pinfunction "~{DTR}_28") (pintype "output+no_connect"))
    )
    (net (code "76") (name "unconnected-(USB-UARTA-~{RI}-Pad2)") (class "Default")
      (node (ref "USB-UART") (pin "2") (pinfunction "~{RI}_2") (pintype "input+no_connect"))
    )
    (net (code "77") (name "unconnected-(USB-UARTA-~{RTS}-Pad24)") (class "Default")
      (node (ref "USB-UART") (pin "24") (pinfunction "~{RTS}_24") (pintype "output+no_connect"))
    )
    (net (code "78") (name "unconnected-(USB-UARTA-~{SUSPEND}-Pad11)") (class "Default")
      (node (ref "USB-UART") (pin "11") (pinfunction "~{SUSPEND}_11") (pintype "output+no_connect"))
    )
    (net (code "79") (name "unconnected-(USBinA-CC1-PadA5)") (class "Default")
      (node (ref "USBin") (pin "A5") (pinfunction "CC1_A5") (pintype "passive"))
    )
    (net (code "80") (name "unconnected-(USBinA-RX2+-PadA11)") (class "Default")
      (node (ref "USBin") (pin "A11") (pinfunction "RX2+_A11") (pintype "passive"))
    )
    (net (code "81") (name "unconnected-(USBinA-RX2--PadA10)") (class "Default")
      (node (ref "USBin") (pin "A10") (pinfunction "RX2-_A10") (pintype "passive"))
    )
    (net (code "82") (name "unconnected-(USBinA-SBU1-PadA8)") (class "Default")
      (node (ref "USBin") (pin "A8") (pinfunction "SBU1_A8") (pintype "passive"))
    )
    (net (code "83") (name "unconnected-(USBinA-TX1+-PadA2)") (class "Default")
      (node (ref "USBin") (pin "A2") (pinfunction "TX1+_A2") (pintype "passive"))
    )
    (net (code "84") (name "unconnected-(USBinA-TX1--PadA3)") (class "Default")
      (node (ref "USBin") (pin "A3") (pinfunction "TX1-_A3") (pintype "passive"))
    )
  )
)
